# AC-DC_3_3_Volt_Power_Supply.net
KiCad netlist of a schematic drawn in EAGLE
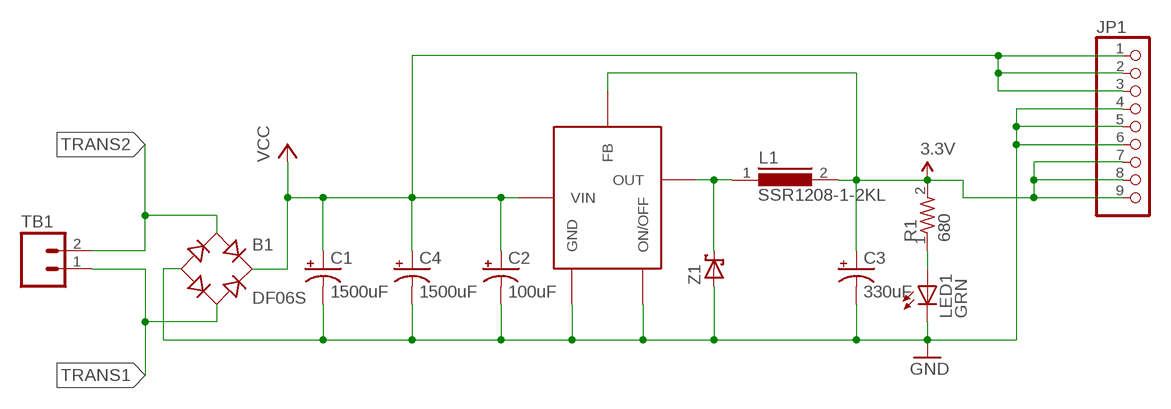
[diagram p0: schematic, sheet 1]

(export (version "E")
  (design (tool "Eeschema 10.0.6"))
  (components
    (comp (ref "B1")
      (value "DF06S")
      (footprint "eagle-import:DFS")
      (libsource (lib "eagle-import") (part "DFS06"))
    )
    (comp (ref "C1")
      (value "1500uF")
      (footprint "eagle-import:CAP_J16")
      (libsource (lib "eagle-import") (part "CAP_POL_J16"))
    )
    (comp (ref "C2")
      (value "100uF")
      (footprint "eagle-import:CAP_F")
      (libsource (lib "eagle-import") (part "CAP_POL_F"))
    )
    (comp (ref "C3")
      (value "330uF")
      (footprint "eagle-import:CAP_F")
      (libsource (lib "eagle-import") (part "CAP_POL_F"))
    )
    (comp (ref "C4")
      (value "1500uF")
      (footprint "eagle-import:CAP_J16")
      (libsource (lib "eagle-import") (part "CAP_POL_J16"))
    )
    (comp (ref "JP1")
      (value "PINHD-1X9")
      (footprint "eagle-import:1X09")
      (libsource (lib "eagle-import") (part "PINHD-1X9"))
    )
    (comp (ref "L1")
      (value "SSR1208-1-2KL")
      (footprint "eagle-import:DR125")
      (libsource (lib "eagle-import") (part "DR125"))
    )
    (comp (ref "LED1")
      (value "GRN")
      (footprint "eagle-import:CHIP-LED0603")
      (libsource (lib "eagle-import") (part "LEDCHIP-LED0603"))
    )
    (comp (ref "R1")
      (value "680")
      (footprint "eagle-import:0603_RESISTOR")
      (libsource (lib "eagle-import") (part "0603_RESISTOR"))
    )
    (comp (ref "REG1")
      (value "TL2575")
      (footprint "eagle-import:TO-263-6")
      (libsource (lib "eagle-import") (part "TL2575"))
    )
    (comp (ref "TB1")
      (value "TERMINAL_BLOCK_2")
      (footprint "eagle-import:TERMINL_BLOCK_2_POS")
      (libsource (lib "eagle-import") (part "TERMINAL_BLOCK_2"))
    )
    (comp (ref "Z1")
      (value "SCHOTTKY_DIODE")
      (footprint "eagle-import:DIODE_SMB")
      (libsource (lib "eagle-import") (part "SCHOTTKY_DIODE"))
    )
  )
  (nets
    (net (code "1") (name "3.3V") (class "Default")
      (node (ref "C3") (pin "+") (pinfunction "+_+") (pintype "passive"))
      (node (ref "JP1") (pin "7") (pinfunction "7_7") (pintype "passive"))
      (node (ref "JP1") (pin "8") (pinfunction "8_8") (pintype "passive"))
      (node (ref "JP1") (pin "9") (pinfunction "9_9") (pintype "passive"))
      (node (ref "L1") (pin "2") (pinfunction "2_2") (pintype "passive"))
      (node (ref "R1") (pin "2") (pinfunction "2_2") (pintype "passive"))
      (node (ref "REG1") (pin "4") (pinfunction "FB_4") (pintype "input"))
    )
    (net (code "2") (name "GND") (class "Default")
      (node (ref "B1") (pin "-") (pinfunction "-_-") (pintype "passive"))
      (node (ref "C1") (pin "1") (pinfunction "-_1") (pintype "passive"))
      (node (ref "C2") (pin "-") (pinfunction "-_-") (pintype "passive"))
      (node (ref "C3") (pin "-") (pinfunction "-_-") (pintype "passive"))
      (node (ref "C4") (pin "1") (pinfunction "-_1") (pintype "passive"))
      (node (ref "JP1") (pin "4") (pinfunction "4_4") (pintype "passive"))
      (node (ref "JP1") (pin "5") (pinfunction "5_5") (pintype "passive"))
      (node (ref "JP1") (pin "6") (pinfunction "6_6") (pintype "passive"))
      (node (ref "LED1") (pin "C") (pinfunction "C_C") (pintype "passive"))
      (node (ref "REG1") (pin "3") (pinfunction "GND_3") (pintype "power_in"))
      (node (ref "REG1") (pin "5") (pinfunction "ON/OFF_5") (pintype "input"))
      (node (ref "Z1") (pin "A") (pinfunction "A_A") (pintype "passive"))
    )
    (net (code "3") (name "Net-(LED1-PadA)") (class "Default")
      (node (ref "LED1") (pin "A") (pinfunction "A_A") (pintype "passive"))
      (node (ref "R1") (pin "1") (pinfunction "1_1") (pintype "passive"))
    )
    (net (code "4") (name "Net-(REG1-OUT)") (class "Default")
      (node (ref "L1") (pin "1") (pinfunction "1_1") (pintype "passive"))
      (node (ref "REG1") (pin "2") (pinfunction "OUT_2") (pintype "power_in"))
      (node (ref "Z1") (pin "C") (pinfunction "C_C") (pintype "passive"))
    )
    (net (code "5") (name "TRANS1") (class "Default")
      (node (ref "B1") (pin "AC2") (pinfunction "AC2_AC2") (pintype "passive"))
      (node (ref "TB1") (pin "1") (pinfunction "1_1") (pintype "passive"))
    )
    (net (code "6") (name "TRANS2") (class "Default")
      (node (ref "B1") (pin "AC1") (pinfunction "AC1_AC1") (pintype "passive"))
      (node (ref "TB1") (pin "2") (pinfunction "2_2") (pintype "passive"))
    )
    (net (code "7") (name "VCC") (class "Default")
      (node (ref "B1") (pin "+") (pinfunction "+_+") (pintype "passive"))
      (node (ref "C1") (pin "2") (pinfunction "+_2") (pintype "passive"))
      (node (ref "C2") (pin "+") (pinfunction "+_+") (pintype "passive"))
      (node (ref "C4") (pin "2") (pinfunction "+_2") (pintype "passive"))
      (node (ref "JP1") (pin "1") (pinfunction "1_1") (pintype "passive"))
      (node (ref "JP1") (pin "2") (pinfunction "2_2") (pintype "passive"))
      (node (ref "JP1") (pin "3") (pinfunction "3_3") (pintype "passive"))
      (node (ref "REG1") (pin "1") (pinfunction "VIN_1") (pintype "power_in"))
    )
  )
)
